# sodonguyenly_end.net
KiCad netlist of a schematic drawn in Altium Designer
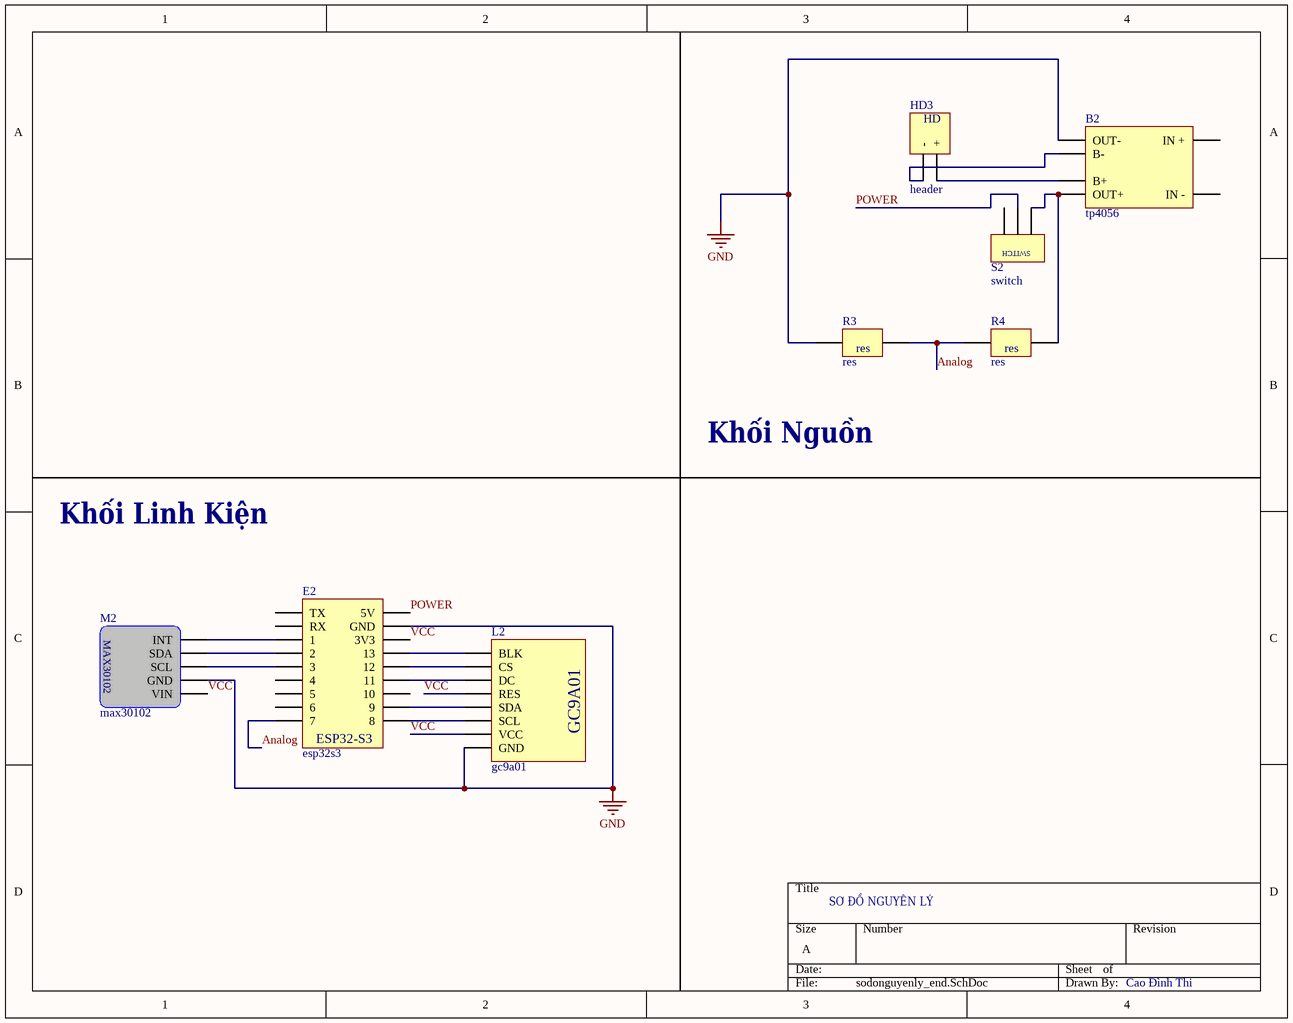
[diagram p0: sodonguyenly_end.SchDoc]

(export (version "E")
  (design (tool "Eeschema 10.0.6"))
  (components
    (comp (ref "B2") (value "tp4056") (footprint "tp4056") (libsource (lib "tp4056") (part "tp4056")))
    (comp (ref "E2") (value "esp32s3") (footprint "esp32s3") (libsource (lib "esp32s3") (part "esp32s3")))
    (comp (ref "HD3") (value "header") (footprint "header") (libsource (lib "header") (part "header")))
    (comp (ref "L2") (value "gc9a01") (footprint "gc9a01") (libsource (lib "gc9a01") (part "gc9a01")))
    (comp (ref "M2") (value "max30102") (footprint "max30102") (libsource (lib "max30102") (part "max30102")))
    (comp (ref "R3") (value "res") (footprint "res") (libsource (lib "res") (part "res")))
    (comp (ref "R4") (value "res") (footprint "res") (libsource (lib "res") (part "res")))
    (comp (ref "S2") (value "switch") (footprint "switch") (libsource (lib "switch") (part "switch")))
  )
  (nets
    (net (code "1") (name "/Analog") (class "Default")
      (node (ref "E2") (pin "8") (pinfunction "7_8") (pintype "passive"))
      (node (ref "R3") (pin "1") (pinfunction "1_1") (pintype "passive"))
      (node (ref "R4") (pin "0") (pinfunction "0_0") (pintype "passive"))
    )
    (net (code "2") (name "/POWER") (class "Default")
      (node (ref "E2") (pin "17") (pinfunction "5V_17") (pintype "passive"))
      (node (ref "S2") (pin "1") (pinfunction "1_1") (pintype "passive"))
    )
    (net (code "3") (name "/VCC") (class "Default")
      (node (ref "E2") (pin "15") (pinfunction "3V3_15") (pintype "passive"))
      (node (ref "L2") (pin "1") (pinfunction "VCC_1") (pintype "passive"))
      (node (ref "L2") (pin "4") (pinfunction "RES_4") (pintype "passive"))
      (node (ref "M2") (pin "4") (pinfunction "VIN_4") (pintype "passive"))
    )
    (net (code "4") (name "GND") (class "Default")
      (node (ref "B2") (pin "2") (pinfunction "OUT-_2") (pintype "passive"))
      (node (ref "E2") (pin "16") (pinfunction "GND_16") (pintype "passive"))
      (node (ref "L2") (pin "0") (pinfunction "GND_0") (pintype "passive"))
      (node (ref "M2") (pin "3") (pinfunction "GND_3") (pintype "passive"))
      (node (ref "R3") (pin "0") (pinfunction "0_0") (pintype "passive"))
    )
    (net (code "5") (name "Net-(B2-B+)") (class "Default")
      (node (ref "B2") (pin "4") (pinfunction "B+_4") (pintype "passive"))
      (node (ref "HD3") (pin "1") (pinfunction "+_1") (pintype "passive"))
    )
    (net (code "6") (name "Net-(B2-B-)") (class "Default")
      (node (ref "B2") (pin "3") (pinfunction "B-_3") (pintype "passive"))
      (node (ref "HD3") (pin "0") (pinfunction "-_0") (pintype "passive"))
    )
    (net (code "7") (name "Net-(B2-OUT+)") (class "Default")
      (node (ref "B2") (pin "5") (pinfunction "OUT+_5") (pintype "passive"))
      (node (ref "R4") (pin "1") (pinfunction "1_1") (pintype "passive"))
      (node (ref "S2") (pin "0") (pinfunction "0_0") (pintype "passive"))
    )
    (net (code "8") (name "Net-(E2-1)") (class "Default")
      (node (ref "E2") (pin "2") (pinfunction "1_2") (pintype "passive"))
      (node (ref "M2") (pin "0") (pinfunction "INT_0") (pintype "passive"))
    )
    (net (code "9") (name "Net-(E2-2)") (class "Default")
      (node (ref "E2") (pin "3") (pinfunction "2_3") (pintype "passive"))
      (node (ref "M2") (pin "1") (pinfunction "SDA_1") (pintype "passive"))
    )
    (net (code "10") (name "Net-(E2-3)") (class "Default")
      (node (ref "E2") (pin "4") (pinfunction "3_4") (pintype "passive"))
      (node (ref "M2") (pin "2") (pinfunction "SCL_2") (pintype "passive"))
    )
    (net (code "11") (name "Net-(E2-8)") (class "Default")
      (node (ref "E2") (pin "9") (pinfunction "8_9") (pintype "passive"))
      (node (ref "L2") (pin "2") (pinfunction "SCL_2") (pintype "passive"))
    )
    (net (code "12") (name "Net-(E2-9)") (class "Default")
      (node (ref "E2") (pin "10") (pinfunction "9_10") (pintype "passive"))
      (node (ref "L2") (pin "3") (pinfunction "SDA_3") (pintype "passive"))
    )
    (net (code "13") (name "Net-(E2-11)") (class "Default")
      (node (ref "E2") (pin "12") (pinfunction "11_12") (pintype "passive"))
      (node (ref "L2") (pin "5") (pinfunction "DC_5") (pintype "passive"))
    )
    (net (code "14") (name "Net-(E2-12)") (class "Default")
      (node (ref "E2") (pin "13") (pinfunction "12_13") (pintype "passive"))
      (node (ref "L2") (pin "6") (pinfunction "CS_6") (pintype "passive"))
    )
    (net (code "15") (name "Net-(E2-13)") (class "Default")
      (node (ref "E2") (pin "14") (pinfunction "13_14") (pintype "passive"))
      (node (ref "L2") (pin "7") (pinfunction "BLK_7") (pintype "passive"))
    )
    (net (code "16") (name "unconnected-(B2-IN_+-Pad0)") (class "Default")
      (node (ref "B2") (pin "0") (pinfunction "IN_+_0") (pintype "passive"))
    )
    (net (code "17") (name "unconnected-(B2-IN_--Pad1)") (class "Default")
      (node (ref "B2") (pin "1") (pinfunction "IN_-_1") (pintype "passive"))
    )
    (net (code "18") (name "unconnected-(E2-4-Pad5)") (class "Default")
      (node (ref "E2") (pin "5") (pinfunction "4_5") (pintype "passive"))
    )
    (net (code "19") (name "unconnected-(E2-5-Pad6)") (class "Default")
      (node (ref "E2") (pin "6") (pinfunction "5_6") (pintype "passive"))
    )
    (net (code "20") (name "unconnected-(E2-6-Pad7)") (class "Default")
      (node (ref "E2") (pin "7") (pinfunction "6_7") (pintype "passive"))
    )
    (net (code "21") (name "unconnected-(E2-10-Pad11)") (class "Default")
      (node (ref "E2") (pin "11") (pinfunction "10_11") (pintype "passive"))
    )
    (net (code "22") (name "unconnected-(E2-RX-Pad1)") (class "Default")
      (node (ref "E2") (pin "1") (pinfunction "RX_1") (pintype "passive"))
    )
    (net (code "23") (name "unconnected-(E2-TX-Pad0)") (class "Default")
      (node (ref "E2") (pin "0") (pinfunction "TX_0") (pintype "passive"))
    )
    (net (code "24") (name "unconnected-(S2-Pad2)") (class "Default")
      (node (ref "S2") (pin "2") (pinfunction "2_2") (pintype "passive"))
    )
  )
)
